# STM32F446RC_single_layer.net
KiCad netlist of a schematic drawn in EAGLE
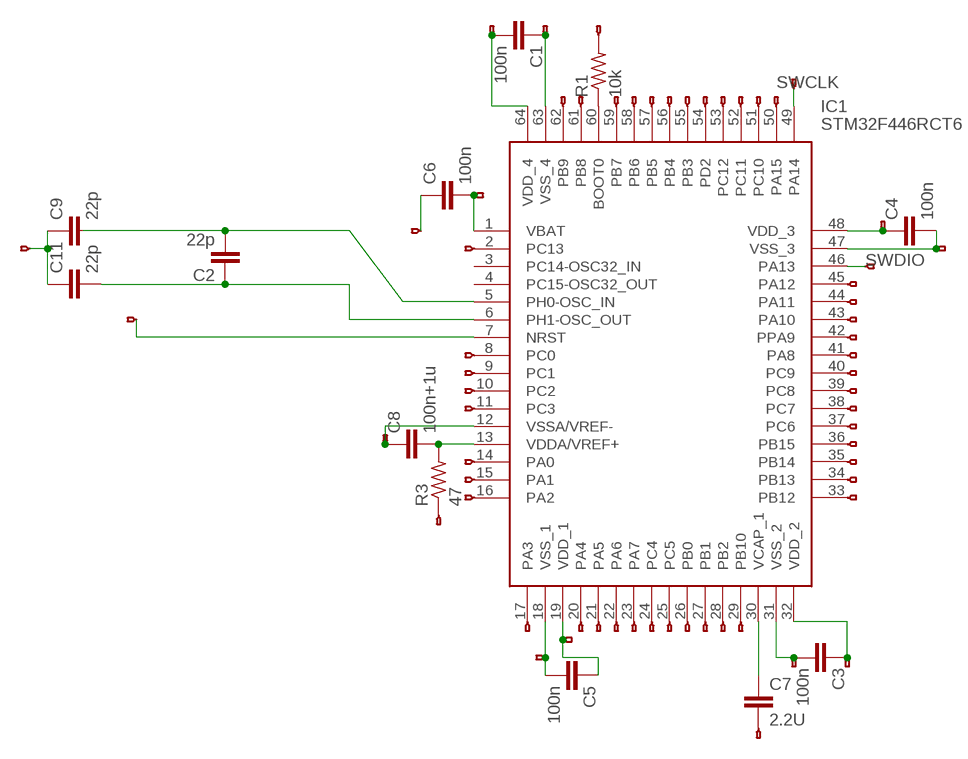
[diagram p0: schematic, sheet 1]

(export (version "E")
  (design (tool "Eeschema 10.0.6"))
  (components
    (comp (ref "C1")
      (value "100n")
      (footprint "eagle-import:C2.5-3")
      (libsource (lib "eagle-import") (part "C2,5-3"))
    )
    (comp (ref "C2")
      (value "22p")
      (footprint "eagle-import:C2.5-3")
      (libsource (lib "eagle-import") (part "C2,5-3"))
    )
    (comp (ref "C3")
      (value "100n")
      (footprint "eagle-import:C2.5-3")
      (libsource (lib "eagle-import") (part "C2,5-3"))
    )
    (comp (ref "C4")
      (value "100n")
      (footprint "eagle-import:C2.5-3")
      (libsource (lib "eagle-import") (part "C2,5-3"))
    )
    (comp (ref "C5")
      (value "100n")
      (footprint "eagle-import:C2.5-3")
      (libsource (lib "eagle-import") (part "C2,5-3"))
    )
    (comp (ref "C6")
      (value "100n")
      (footprint "eagle-import:C2.5-3")
      (libsource (lib "eagle-import") (part "C2,5-3"))
    )
    (comp (ref "C7")
      (value "2.2U")
      (footprint "eagle-import:C2.5-3")
      (libsource (lib "eagle-import") (part "C2,5-3"))
    )
    (comp (ref "C8")
      (value "100n+1u")
      (footprint "eagle-import:C2.5-3")
      (libsource (lib "eagle-import") (part "C2,5-3"))
    )
    (comp (ref "C9")
      (value "22p")
      (footprint "eagle-import:C2.5-3")
      (libsource (lib "eagle-import") (part "C2,5-3"))
    )
    (comp (ref "C11")
      (value "22p")
      (footprint "eagle-import:C2.5-3")
      (libsource (lib "eagle-import") (part "C2,5-3"))
    )
    (comp (ref "IC1")
      (value "STM32F446RCT6")
      (footprint "eagle-import:QFP50P1200X1200X160-64N")
      (fields (field (name "MOUSER_PART_NUMBER") "511-STM32F446RCT6"))
      (libsource (lib "eagle-import") (part "STM32F446RCT6"))
    )
    (comp (ref "JP1")
      (value "HEADERHOLE-HEADERHOLE")
      (footprint "eagle-import:1X1-HEADER-HOLE")
      (libsource (lib "eagle-import") (part "HEADERHOLE-HEADERHOLE"))
    )
    (comp (ref "JP2")
      (value "HEADERHOLE-HEADERHOLE")
      (footprint "eagle-import:1X1-HEADER-HOLE")
      (libsource (lib "eagle-import") (part "HEADERHOLE-HEADERHOLE"))
    )
    (comp (ref "JP3")
      (value "HEADERHOLE-HEADERHOLE")
      (footprint "eagle-import:1X1-HEADER-HOLE")
      (libsource (lib "eagle-import") (part "HEADERHOLE-HEADERHOLE"))
    )
    (comp (ref "JP4")
      (value "HEADERHOLE-HEADERHOLE")
      (footprint "eagle-import:1X1-HEADER-HOLE")
      (libsource (lib "eagle-import") (part "HEADERHOLE-HEADERHOLE"))
    )
    (comp (ref "JP5")
      (value "HEADERHOLE-HEADERHOLE")
      (footprint "eagle-import:1X1-HEADER-HOLE")
      (libsource (lib "eagle-import") (part "HEADERHOLE-HEADERHOLE"))
    )
    (comp (ref "JP6")
      (value "HEADERHOLE-HEADERHOLE")
      (footprint "eagle-import:1X1-HEADER-HOLE")
      (libsource (lib "eagle-import") (part "HEADERHOLE-HEADERHOLE"))
    )
    (comp (ref "JP7")
      (value "HEADERHOLE-HEADERHOLE")
      (footprint "eagle-import:1X1-HEADER-HOLE")
      (libsource (lib "eagle-import") (part "HEADERHOLE-HEADERHOLE"))
    )
    (comp (ref "JP9")
      (value "HEADERHOLE-HEADERHOLE")
      (footprint "eagle-import:1X1-HEADER-HOLE")
      (libsource (lib "eagle-import") (part "HEADERHOLE-HEADERHOLE"))
    )
    (comp (ref "JP10")
      (value "HEADERHOLE-HEADERHOLE")
      (footprint "eagle-import:1X1-HEADER-HOLE")
      (libsource (lib "eagle-import") (part "HEADERHOLE-HEADERHOLE"))
    )
    (comp (ref "JP11")
      (value "HEADERHOLE-HEADERHOLE")
      (footprint "eagle-import:1X1-HEADER-HOLE")
      (libsource (lib "eagle-import") (part "HEADERHOLE-HEADERHOLE"))
    )
    (comp (ref "JP12")
      (value "HEADERHOLE-HEADERHOLE")
      (footprint "eagle-import:1X1-HEADER-HOLE")
      (libsource (lib "eagle-import") (part "HEADERHOLE-HEADERHOLE"))
    )
    (comp (ref "JP13")
      (value "HEADERHOLE-HEADERHOLE")
      (footprint "eagle-import:1X1-HEADER-HOLE")
      (libsource (lib "eagle-import") (part "HEADERHOLE-HEADERHOLE"))
    )
    (comp (ref "JP14")
      (value "HEADERHOLE-HEADERHOLE")
      (footprint "eagle-import:1X1-HEADER-HOLE")
      (libsource (lib "eagle-import") (part "HEADERHOLE-HEADERHOLE"))
    )
    (comp (ref "JP15")
      (value "HEADERHOLE-HEADERHOLE")
      (footprint "eagle-import:1X1-HEADER-HOLE")
      (libsource (lib "eagle-import") (part "HEADERHOLE-HEADERHOLE"))
    )
    (comp (ref "JP16")
      (value "HEADERHOLE-HEADERHOLE")
      (footprint "eagle-import:1X1-HEADER-HOLE")
      (libsource (lib "eagle-import") (part "HEADERHOLE-HEADERHOLE"))
    )
    (comp (ref "JP17")
      (value "HEADERHOLE-HEADERHOLE")
      (footprint "eagle-import:1X1-HEADER-HOLE")
      (libsource (lib "eagle-import") (part "HEADERHOLE-HEADERHOLE"))
    )
    (comp (ref "JP18")
      (value "HEADERHOLE-HEADERHOLE")
      (footprint "eagle-import:1X1-HEADER-HOLE")
      (libsource (lib "eagle-import") (part "HEADERHOLE-HEADERHOLE"))
    )
    (comp (ref "JP19")
      (value "HEADERHOLE-HEADERHOLE")
      (footprint "eagle-import:1X1-HEADER-HOLE")
      (libsource (lib "eagle-import") (part "HEADERHOLE-HEADERHOLE"))
    )
    (comp (ref "JP20")
      (value "HEADERHOLE-HEADERHOLE")
      (footprint "eagle-import:1X1-HEADER-HOLE")
      (libsource (lib "eagle-import") (part "HEADERHOLE-HEADERHOLE"))
    )
    (comp (ref "JP21")
      (value "HEADERHOLE-HEADERHOLE")
      (footprint "eagle-import:1X1-HEADER-HOLE")
      (libsource (lib "eagle-import") (part "HEADERHOLE-HEADERHOLE"))
    )
    (comp (ref "JP22")
      (value "HEADERHOLE-HEADERHOLE")
      (footprint "eagle-import:1X1-HEADER-HOLE")
      (libsource (lib "eagle-import") (part "HEADERHOLE-HEADERHOLE"))
    )
    (comp (ref "JP23")
      (value "HEADERHOLE-HEADERHOLE")
      (footprint "eagle-import:1X1-HEADER-HOLE")
      (libsource (lib "eagle-import") (part "HEADERHOLE-HEADERHOLE"))
    )
    (comp (ref "JP24")
      (value "HEADERHOLE-HEADERHOLE")
      (footprint "eagle-import:1X1-HEADER-HOLE")
      (libsource (lib "eagle-import") (part "HEADERHOLE-HEADERHOLE"))
    )
    (comp (ref "JP25")
      (value "HEADERHOLE-HEADERHOLE")
      (footprint "eagle-import:1X1-HEADER-HOLE")
      (libsource (lib "eagle-import") (part "HEADERHOLE-HEADERHOLE"))
    )
    (comp (ref "JP26")
      (value "HEADERHOLE-HEADERHOLE")
      (footprint "eagle-import:1X1-HEADER-HOLE")
      (libsource (lib "eagle-import") (part "HEADERHOLE-HEADERHOLE"))
    )
    (comp (ref "JP27")
      (value "HEADERHOLE-HEADERHOLE")
      (footprint "eagle-import:1X1-HEADER-HOLE")
      (libsource (lib "eagle-import") (part "HEADERHOLE-HEADERHOLE"))
    )
    (comp (ref "JP28")
      (value "HEADERHOLE-HEADERHOLE")
      (footprint "eagle-import:1X1-HEADER-HOLE")
      (libsource (lib "eagle-import") (part "HEADERHOLE-HEADERHOLE"))
    )
    (comp (ref "JP29")
      (value "HEADERHOLE-HEADERHOLE")
      (footprint "eagle-import:1X1-HEADER-HOLE")
      (libsource (lib "eagle-import") (part "HEADERHOLE-HEADERHOLE"))
    )
    (comp (ref "JP30")
      (value "HEADERHOLE-HEADERHOLE")
      (footprint "eagle-import:1X1-HEADER-HOLE")
      (libsource (lib "eagle-import") (part "HEADERHOLE-HEADERHOLE"))
    )
    (comp (ref "JP31")
      (value "HEADERHOLE-HEADERHOLE")
      (footprint "eagle-import:1X1-HEADER-HOLE")
      (libsource (lib "eagle-import") (part "HEADERHOLE-HEADERHOLE"))
    )
    (comp (ref "JP32")
      (value "HEADERHOLE-HEADERHOLE")
      (footprint "eagle-import:1X1-HEADER-HOLE")
      (libsource (lib "eagle-import") (part "HEADERHOLE-HEADERHOLE"))
    )
    (comp (ref "JP33")
      (value "HEADERHOLE-HEADERHOLE")
      (footprint "eagle-import:1X1-HEADER-HOLE")
      (libsource (lib "eagle-import") (part "HEADERHOLE-HEADERHOLE"))
    )
    (comp (ref "JP34")
      (value "HEADERHOLE-HEADERHOLE")
      (footprint "eagle-import:1X1-HEADER-HOLE")
      (libsource (lib "eagle-import") (part "HEADERHOLE-HEADERHOLE"))
    )
    (comp (ref "JP35")
      (value "HEADERHOLE-HEADERHOLE")
      (footprint "eagle-import:1X1-HEADER-HOLE")
      (libsource (lib "eagle-import") (part "HEADERHOLE-HEADERHOLE"))
    )
    (comp (ref "JP36")
      (value "HEADERHOLE-HEADERHOLE")
      (footprint "eagle-import:1X1-HEADER-HOLE")
      (libsource (lib "eagle-import") (part "HEADERHOLE-HEADERHOLE"))
    )
    (comp (ref "JP37")
      (value "HEADERHOLE-HEADERHOLE")
      (footprint "eagle-import:1X1-HEADER-HOLE")
      (libsource (lib "eagle-import") (part "HEADERHOLE-HEADERHOLE"))
    )
    (comp (ref "JP38")
      (value "HEADERHOLE-HEADERHOLE")
      (footprint "eagle-import:1X1-HEADER-HOLE")
      (libsource (lib "eagle-import") (part "HEADERHOLE-HEADERHOLE"))
    )
    (comp (ref "JP39")
      (value "HEADERHOLE-HEADERHOLE")
      (footprint "eagle-import:1X1-HEADER-HOLE")
      (libsource (lib "eagle-import") (part "HEADERHOLE-HEADERHOLE"))
    )
    (comp (ref "JP40")
      (value "HEADERHOLE-HEADERHOLE")
      (footprint "eagle-import:1X1-HEADER-HOLE")
      (libsource (lib "eagle-import") (part "HEADERHOLE-HEADERHOLE"))
    )
    (comp (ref "JP41")
      (value "HEADERHOLE-HEADERHOLE")
      (footprint "eagle-import:1X1-HEADER-HOLE")
      (libsource (lib "eagle-import") (part "HEADERHOLE-HEADERHOLE"))
    )
    (comp (ref "JP42")
      (value "HEADERHOLE-HEADERHOLE")
      (footprint "eagle-import:1X1-HEADER-HOLE")
      (libsource (lib "eagle-import") (part "HEADERHOLE-HEADERHOLE"))
    )
    (comp (ref "JP43")
      (value "HEADERHOLE-HEADERHOLE")
      (footprint "eagle-import:1X1-HEADER-HOLE")
      (libsource (lib "eagle-import") (part "HEADERHOLE-HEADERHOLE"))
    )
    (comp (ref "JP44")
      (value "HEADERHOLE-HEADERHOLE")
      (footprint "eagle-import:1X1-HEADER-HOLE")
      (libsource (lib "eagle-import") (part "HEADERHOLE-HEADERHOLE"))
    )
    (comp (ref "JP45")
      (value "HEADERHOLE-HEADERHOLE")
      (footprint "eagle-import:1X1-HEADER-HOLE")
      (libsource (lib "eagle-import") (part "HEADERHOLE-HEADERHOLE"))
    )
    (comp (ref "JP46")
      (value "HEADERHOLE-HEADERHOLE")
      (footprint "eagle-import:1X1-HEADER-HOLE")
      (libsource (lib "eagle-import") (part "HEADERHOLE-HEADERHOLE"))
    )
    (comp (ref "JP47")
      (value "HEADERHOLE-HEADERHOLE")
      (footprint "eagle-import:1X1-HEADER-HOLE")
      (libsource (lib "eagle-import") (part "HEADERHOLE-HEADERHOLE"))
    )
    (comp (ref "JP48")
      (value "HEADERHOLE-HEADERHOLE")
      (footprint "eagle-import:1X1-HEADER-HOLE")
      (libsource (lib "eagle-import") (part "HEADERHOLE-HEADERHOLE"))
    )
    (comp (ref "JP49")
      (value "HEADERHOLE-HEADERHOLE")
      (footprint "eagle-import:1X1-HEADER-HOLE")
      (libsource (lib "eagle-import") (part "HEADERHOLE-HEADERHOLE"))
    )
    (comp (ref "JP50")
      (value "HEADERHOLE-HEADERHOLE")
      (footprint "eagle-import:1X1-HEADER-HOLE")
      (libsource (lib "eagle-import") (part "HEADERHOLE-HEADERHOLE"))
    )
    (comp (ref "JP51")
      (value "HEADERHOLE-HEADERHOLE")
      (footprint "eagle-import:1X1-HEADER-HOLE")
      (libsource (lib "eagle-import") (part "HEADERHOLE-HEADERHOLE"))
    )
    (comp (ref "JP52")
      (value "HEADERHOLE-HEADERHOLE")
      (footprint "eagle-import:1X1-HEADER-HOLE")
      (libsource (lib "eagle-import") (part "HEADERHOLE-HEADERHOLE"))
    )
    (comp (ref "JP53")
      (value "HEADERHOLE-HEADERHOLE")
      (footprint "eagle-import:1X1-HEADER-HOLE")
      (libsource (lib "eagle-import") (part "HEADERHOLE-HEADERHOLE"))
    )
    (comp (ref "JP54")
      (value "HEADERHOLE-HEADERHOLE")
      (footprint "eagle-import:1X1-HEADER-HOLE")
      (libsource (lib "eagle-import") (part "HEADERHOLE-HEADERHOLE"))
    )
    (comp (ref "JP55")
      (value "HEADERHOLE-HEADERHOLE")
      (footprint "eagle-import:1X1-HEADER-HOLE")
      (libsource (lib "eagle-import") (part "HEADERHOLE-HEADERHOLE"))
    )
    (comp (ref "JP56")
      (value "HEADERHOLE-HEADERHOLE")
      (footprint "eagle-import:1X1-HEADER-HOLE")
      (libsource (lib "eagle-import") (part "HEADERHOLE-HEADERHOLE"))
    )
    (comp (ref "JP57")
      (value "HEADERHOLE-HEADERHOLE")
      (footprint "eagle-import:1X1-HEADER-HOLE")
      (libsource (lib "eagle-import") (part "HEADERHOLE-HEADERHOLE"))
    )
    (comp (ref "JP58")
      (value "HEADERHOLE-HEADERHOLE")
      (footprint "eagle-import:1X1-HEADER-HOLE")
      (libsource (lib "eagle-import") (part "HEADERHOLE-HEADERHOLE"))
    )
    (comp (ref "JP59")
      (value "HEADERHOLE-HEADERHOLE")
      (footprint "eagle-import:1X1-HEADER-HOLE")
      (libsource (lib "eagle-import") (part "HEADERHOLE-HEADERHOLE"))
    )
    (comp (ref "JP61")
      (value "HEADERHOLE-HEADERHOLE")
      (footprint "eagle-import:1X1-HEADER-HOLE")
      (libsource (lib "eagle-import") (part "HEADERHOLE-HEADERHOLE"))
    )
    (comp (ref "JP62")
      (value "HEADERHOLE-HEADERHOLE")
      (footprint "eagle-import:1X1-HEADER-HOLE")
      (libsource (lib "eagle-import") (part "HEADERHOLE-HEADERHOLE"))
    )
    (comp (ref "JP63")
      (value "HEADERHOLE-HEADERHOLE")
      (footprint "eagle-import:1X1-HEADER-HOLE")
      (libsource (lib "eagle-import") (part "HEADERHOLE-HEADERHOLE"))
    )
    (comp (ref "JP65")
      (value "HEADERHOLE-HEADERHOLE")
      (footprint "eagle-import:1X1-HEADER-HOLE")
      (libsource (lib "eagle-import") (part "HEADERHOLE-HEADERHOLE"))
    )
    (comp (ref "R1")
      (value "10k")
      (footprint "eagle-import:0204V")
      (libsource (lib "eagle-import") (part "R-US_0204/2V"))
    )
    (comp (ref "R3")
      (value "47")
      (footprint "eagle-import:0204V")
      (libsource (lib "eagle-import") (part "R-US_0204/2V"))
    )
  )
  (nets
    (net (code "1") (name "/SWCLK") (class "Default")
      (node (ref "IC1") (pin "49") (pinfunction "PA14_49") (pintype "bidirectional"))
      (node (ref "JP55") (pin "1") (pinfunction "P$1_1") (pintype "bidirectional"))
    )
    (net (code "2") (name "/SWDIO") (class "Default")
      (node (ref "IC1") (pin "46") (pinfunction "PA13_46") (pintype "bidirectional"))
      (node (ref "JP54") (pin "1") (pinfunction "P$1_1") (pintype "bidirectional"))
    )
    (net (code "3") (name "Net-(IC1-BOOT0)") (class "Default")
      (node (ref "IC1") (pin "60") (pinfunction "BOOT0_60") (pintype "bidirectional"))
      (node (ref "R1") (pin "1") (pinfunction "1_1") (pintype "passive"))
    )
    (net (code "4") (name "Net-(IC1-NRST)") (class "Default")
      (node (ref "IC1") (pin "7") (pinfunction "NRST_7") (pintype "bidirectional"))
      (node (ref "JP63") (pin "1") (pinfunction "P$1_1") (pintype "bidirectional"))
    )
    (net (code "5") (name "Net-(IC1-PA0)") (class "Default")
      (node (ref "IC1") (pin "14") (pinfunction "PA0_14") (pintype "bidirectional"))
      (node (ref "JP34") (pin "1") (pinfunction "P$1_1") (pintype "bidirectional"))
    )
    (net (code "6") (name "Net-(IC1-PA1)") (class "Default")
      (node (ref "IC1") (pin "15") (pinfunction "PA1_15") (pintype "bidirectional"))
      (node (ref "JP35") (pin "1") (pinfunction "P$1_1") (pintype "bidirectional"))
    )
    (net (code "7") (name "Net-(IC1-PA2)") (class "Default")
      (node (ref "IC1") (pin "16") (pinfunction "PA2_16") (pintype "bidirectional"))
      (node (ref "JP36") (pin "1") (pinfunction "P$1_1") (pintype "bidirectional"))
    )
    (net (code "8") (name "Net-(IC1-PA3)") (class "Default")
      (node (ref "IC1") (pin "17") (pinfunction "PA3_17") (pintype "bidirectional"))
      (node (ref "JP24") (pin "1") (pinfunction "P$1_1") (pintype "bidirectional"))
    )
    (net (code "9") (name "Net-(IC1-PA4)") (class "Default")
      (node (ref "IC1") (pin "20") (pinfunction "PA4_20") (pintype "bidirectional"))
      (node (ref "JP21") (pin "1") (pinfunction "P$1_1") (pintype "bidirectional"))
    )
    (net (code "10") (name "Net-(IC1-PA5)") (class "Default")
      (node (ref "IC1") (pin "21") (pinfunction "PA5_21") (pintype "bidirectional"))
      (node (ref "JP19") (pin "1") (pinfunction "P$1_1") (pintype "bidirectional"))
    )
    (net (code "11") (name "Net-(IC1-PA6)") (class "Default")
      (node (ref "IC1") (pin "22") (pinfunction "PA6_22") (pintype "bidirectional"))
      (node (ref "JP9") (pin "1") (pinfunction "P$1_1") (pintype "bidirectional"))
    )
    (net (code "12") (name "Net-(IC1-PA7)") (class "Default")
      (node (ref "IC1") (pin "23") (pinfunction "PA7_23") (pintype "bidirectional"))
      (node (ref "JP11") (pin "1") (pinfunction "P$1_1") (pintype "bidirectional"))
    )
    (net (code "13") (name "Net-(IC1-PA8)") (class "Default")
      (node (ref "IC1") (pin "41") (pinfunction "PA8_41") (pintype "bidirectional"))
      (node (ref "JP28") (pin "1") (pinfunction "P$1_1") (pintype "bidirectional"))
    )
    (net (code "14") (name "Net-(IC1-PA10)") (class "Default")
      (node (ref "IC1") (pin "43") (pinfunction "PA10_43") (pintype "bidirectional"))
      (node (ref "JP33") (pin "1") (pinfunction "P$1_1") (pintype "bidirectional"))
    )
    (net (code "15") (name "Net-(IC1-PA11)") (class "Default")
      (node (ref "IC1") (pin "44") (pinfunction "PA11_44") (pintype "bidirectional"))
      (node (ref "JP32") (pin "1") (pinfunction "P$1_1") (pintype "bidirectional"))
    )
    (net (code "16") (name "Net-(IC1-PA12)") (class "Default")
      (node (ref "IC1") (pin "45") (pinfunction "PA12_45") (pintype "bidirectional"))
      (node (ref "JP25") (pin "1") (pinfunction "P$1_1") (pintype "bidirectional"))
    )
    (net (code "17") (name "Net-(IC1-PA15)") (class "Default")
      (node (ref "IC1") (pin "50") (pinfunction "PA15_50") (pintype "bidirectional"))
      (node (ref "JP45") (pin "1") (pinfunction "P$1_1") (pintype "bidirectional"))
    )
    (net (code "18") (name "Net-(IC1-PB0)") (class "Default")
      (node (ref "IC1") (pin "26") (pinfunction "PB0_26") (pintype "bidirectional"))
      (node (ref "JP22") (pin "1") (pinfunction "P$1_1") (pintype "bidirectional"))
    )
    (net (code "19") (name "Net-(IC1-PB1)") (class "Default")
      (node (ref "IC1") (pin "27") (pinfunction "PB1_27") (pintype "bidirectional"))
      (node (ref "JP17") (pin "1") (pinfunction "P$1_1") (pintype "bidirectional"))
    )
    (net (code "20") (name "Net-(IC1-PB2)") (class "Default")
      (node (ref "IC1") (pin "28") (pinfunction "PB2_28") (pintype "bidirectional"))
      (node (ref "JP16") (pin "1") (pinfunction "P$1_1") (pintype "bidirectional"))
    )
    (net (code "21") (name "Net-(IC1-PB3)") (class "Default")
      (node (ref "IC1") (pin "55") (pinfunction "PB3_55") (pintype "bidirectional"))
      (node (ref "JP44") (pin "1") (pinfunction "P$1_1") (pintype "bidirectional"))
    )
    (net (code "22") (name "Net-(IC1-PB4)") (class "Default")
      (node (ref "IC1") (pin "56") (pinfunction "PB4_56") (pintype "bidirectional"))
      (node (ref "JP40") (pin "1") (pinfunction "P$1_1") (pintype "bidirectional"))
    )
    (net (code "23") (name "Net-(IC1-PB5)") (class "Default")
      (node (ref "IC1") (pin "57") (pinfunction "PB5_57") (pintype "bidirectional"))
      (node (ref "JP41") (pin "1") (pinfunction "P$1_1") (pintype "bidirectional"))
    )
    (net (code "24") (name "Net-(IC1-PB6)") (class "Default")
      (node (ref "IC1") (pin "58") (pinfunction "PB6_58") (pintype "bidirectional"))
      (node (ref "JP42") (pin "1") (pinfunction "P$1_1") (pintype "bidirectional"))
    )
    (net (code "25") (name "Net-(IC1-PB7)") (class "Default")
      (node (ref "IC1") (pin "59") (pinfunction "PB7_59") (pintype "bidirectional"))
      (node (ref "JP43") (pin "1") (pinfunction "P$1_1") (pintype "bidirectional"))
    )
    (net (code "26") (name "Net-(IC1-PB8)") (class "Default")
      (node (ref "IC1") (pin "61") (pinfunction "PB8_61") (pintype "bidirectional"))
      (node (ref "JP46") (pin "1") (pinfunction "P$1_1") (pintype "bidirectional"))
    )
    (net (code "27") (name "Net-(IC1-PB9)") (class "Default")
      (node (ref "IC1") (pin "62") (pinfunction "PB9_62") (pintype "bidirectional"))
      (node (ref "JP47") (pin "1") (pinfunction "P$1_1") (pintype "bidirectional"))
    )
    (net (code "28") (name "Net-(IC1-PB10)") (class "Default")
      (node (ref "IC1") (pin "29") (pinfunction "PB10_29") (pintype "bidirectional"))
      (node (ref "JP14") (pin "1") (pinfunction "P$1_1") (pintype "bidirectional"))
    )
    (net (code "29") (name "Net-(IC1-PB12)") (class "Default")
      (node (ref "IC1") (pin "33") (pinfunction "PB12_33") (pintype "bidirectional"))
      (node (ref "JP18") (pin "1") (pinfunction "P$1_1") (pintype "bidirectional"))
    )
    (net (code "30") (name "Net-(IC1-PB13)") (class "Default")
      (node (ref "IC1") (pin "34") (pinfunction "PB13_34") (pintype "bidirectional"))
      (node (ref "JP13") (pin "1") (pinfunction "P$1_1") (pintype "bidirectional"))
    )
    (net (code "31") (name "Net-(IC1-PB14)") (class "Default")
      (node (ref "IC1") (pin "35") (pinfunction "PB14_35") (pintype "bidirectional"))
      (node (ref "JP6") (pin "1") (pinfunction "P$1_1") (pintype "bidirectional"))
    )
    (net (code "32") (name "Net-(IC1-PB15)") (class "Default")
      (node (ref "IC1") (pin "36") (pinfunction "PB15_36") (pintype "bidirectional"))
      (node (ref "JP10") (pin "1") (pinfunction "P$1_1") (pintype "bidirectional"))
    )
    (net (code "33") (name "Net-(IC1-PC0)") (class "Default")
      (node (ref "IC1") (pin "8") (pinfunction "PC0_8") (pintype "bidirectional"))
      (node (ref "JP29") (pin "1") (pinfunction "P$1_1") (pintype "bidirectional"))
    )
    (net (code "34") (name "Net-(IC1-PC1)") (class "Default")
      (node (ref "IC1") (pin "9") (pinfunction "PC1_9") (pintype "bidirectional"))
      (node (ref "JP27") (pin "1") (pinfunction "P$1_1") (pintype "bidirectional"))
    )
    (net (code "35") (name "Net-(IC1-PC2)") (class "Default")
      (node (ref "IC1") (pin "10") (pinfunction "PC2_10") (pintype "bidirectional"))
      (node (ref "JP3") (pin "1") (pinfunction "P$1_1") (pintype "bidirectional"))
    )
    (net (code "36") (name "Net-(IC1-PC3)") (class "Default")
      (node (ref "IC1") (pin "11") (pinfunction "PC3_11") (pintype "bidirectional"))
      (node (ref "JP4") (pin "1") (pinfunction "P$1_1") (pintype "bidirectional"))
    )
    (net (code "37") (name "Net-(IC1-PC4)") (class "Default")
      (node (ref "IC1") (pin "24") (pinfunction "PC4_24") (pintype "bidirectional"))
      (node (ref "JP12") (pin "1") (pinfunction "P$1_1") (pintype "bidirectional"))
    )
    (net (code "38") (name "Net-(IC1-PC5)") (class "Default")
      (node (ref "IC1") (pin "25") (pinfunction "PC5_25") (pintype "bidirectional"))
      (node (ref "JP23") (pin "1") (pinfunction "P$1_1") (pintype "bidirectional"))
    )
    (net (code "39") (name "Net-(IC1-PC6)") (class "Default")
      (node (ref "IC1") (pin "37") (pinfunction "PC6_37") (pintype "bidirectional"))
      (node (ref "JP1") (pin "1") (pinfunction "P$1_1") (pintype "bidirectional"))
    )
    (net (code "40") (name "Net-(IC1-PC7)") (class "Default")
      (node (ref "IC1") (pin "38") (pinfunction "PC7_38") (pintype "bidirectional"))
      (node (ref "JP15") (pin "1") (pinfunction "P$1_1") (pintype "bidirectional"))
    )
    (net (code "41") (name "Net-(IC1-PC8)") (class "Default")
      (node (ref "IC1") (pin "39") (pinfunction "PC8_39") (pintype "bidirectional"))
      (node (ref "JP2") (pin "1") (pinfunction "P$1_1") (pintype "bidirectional"))
    )
    (net (code "42") (name "Net-(IC1-PC9)") (class "Default")
      (node (ref "IC1") (pin "40") (pinfunction "PC9_40") (pintype "bidirectional"))
      (node (ref "JP30") (pin "1") (pinfunction "P$1_1") (pintype "bidirectional"))
    )
    (net (code "43") (name "Net-(IC1-PC10)") (class "Default")
      (node (ref "IC1") (pin "51") (pinfunction "PC10_51") (pintype "bidirectional"))
      (node (ref "JP37") (pin "1") (pinfunction "P$1_1") (pintype "bidirectional"))
    )
    (net (code "44") (name "Net-(IC1-PC11)") (class "Default")
      (node (ref "IC1") (pin "52") (pinfunction "PC11_52") (pintype "bidirectional"))
      (node (ref "JP5") (pin "1") (pinfunction "P$1_1") (pintype "bidirectional"))
    )
    (net (code "45") (name "Net-(IC1-PC12)") (class "Default")
      (node (ref "IC1") (pin "53") (pinfunction "PC12_53") (pintype "bidirectional"))
      (node (ref "JP39") (pin "1") (pinfunction "P$1_1") (pintype "bidirectional"))
    )
    (net (code "46") (name "Net-(IC1-PC13)") (class "Default")
      (node (ref "IC1") (pin "2") (pinfunction "PC13_2") (pintype "bidirectional"))
      (node (ref "JP26") (pin "1") (pinfunction "P$1_1") (pintype "bidirectional"))
    )
    (net (code "47") (name "Net-(IC1-PD2)") (class "Default")
      (node (ref "IC1") (pin "54") (pinfunction "PD2_54") (pintype "bidirectional"))
      (node (ref "JP38") (pin "1") (pinfunction "P$1_1") (pintype "bidirectional"))
    )
    (net (code "48") (name "Net-(IC1-PH0-OSC_IN)") (class "Default")
      (node (ref "C2") (pin "2") (pinfunction "2_2") (pintype "passive"))
      (node (ref "IC1") (pin "5") (pinfunction "PH0-OSC_IN_5") (pintype "bidirectional"))
    )
    (net (code "49") (name "Net-(IC1-PH1-OSC_OUT)") (class "Default")
      (node (ref "C11") (pin "2") (pinfunction "2_2") (pintype "passive"))
      (node (ref "C2") (pin "1") (pinfunction "1_1") (pintype "passive"))
      (node (ref "IC1") (pin "6") (pinfunction "PH1-OSC_OUT_6") (pintype "bidirectional"))
    )
    (net (code "50") (name "Net-(IC1-PPA9)") (class "Default")
      (node (ref "IC1") (pin "42") (pinfunction "PPA9_42") (pintype "bidirectional"))
      (node (ref "JP31") (pin "1") (pinfunction "P$1_1") (pintype "bidirectional"))
    )
    (net (code "51") (name "Net-(IC1-VBAT)") (class "Default")
      (node (ref "C6") (pin "2") (pinfunction "2_2") (pintype "passive"))
      (node (ref "IC1") (pin "1") (pinfunction "VBAT_1") (pintype "bidirectional"))
      (node (ref "JP7") (pin "1") (pinfunction "P$1_1") (pintype "bidirectional"))
    )
    (net (code "52") (name "Net-(IC1-VCAP_1)") (class "Default")
      (node (ref "C7") (pin "1") (pinfunction "1_1") (pintype "passive"))
      (node (ref "IC1") (pin "30") (pinfunction "VCAP_1_30") (pintype "bidirectional"))
    )
    (net (code "53") (name "Net-(IC1-VDDA{slash}VREF+)") (class "Default")
      (node (ref "C8") (pin "2") (pinfunction "2_2") (pintype "passive"))
      (node (ref "IC1") (pin "13") (pinfunction "VDDA/VREF+_13") (pintype "bidirectional"))
      (node (ref "R3") (pin "2") (pinfunction "2_2") (pintype "passive"))
    )
    (net (code "54") (name "Net-(IC1-VDD_1)") (class "Default")
      (node (ref "C5") (pin "1") (pinfunction "1_1") (pintype "passive"))
      (node (ref "IC1") (pin "19") (pinfunction "VDD_1_19") (pintype "bidirectional"))
      (node (ref "JP48") (pin "1") (pinfunction "P$1_1") (pintype "bidirectional"))
    )
    (net (code "55") (name "Net-(IC1-VDD_2)") (class "Default")
      (node (ref "C3") (pin "1") (pinfunction "1_1") (pintype "passive"))
      (node (ref "IC1") (pin "32") (pinfunction "VDD_2_32") (pintype "bidirectional"))
      (node (ref "JP51") (pin "1") (pinfunction "P$1_1") (pintype "bidirectional"))
    )
    (net (code "56") (name "Net-(IC1-VDD_3)") (class "Default")
      (node (ref "C4") (pin "1") (pinfunction "1_1") (pintype "passive"))
      (node (ref "IC1") (pin "48") (pinfunction "VDD_3_48") (pintype "bidirectional"))
      (node (ref "JP53") (pin "1") (pinfunction "P$1_1") (pintype "bidirectional"))
    )
    (net (code "57") (name "Net-(IC1-VDD_4)") (class "Default")
      (node (ref "C1") (pin "2") (pinfunction "2_2") (pintype "passive"))
      (node (ref "IC1") (pin "64") (pinfunction "VDD_4_64") (pintype "bidirectional"))
      (node (ref "JP58") (pin "1") (pinfunction "P$1_1") (pintype "bidirectional"))
    )
    (net (code "58") (name "Net-(IC1-VSSA{slash}VREF-)") (class "Default")
      (node (ref "C8") (pin "1") (pinfunction "1_1") (pintype "passive"))
      (node (ref "IC1") (pin "12") (pinfunction "VSSA/VREF-_12") (pintype "bidirectional"))
      (node (ref "JP62") (pin "1") (pinfunction "P$1_1") (pintype "bidirectional"))
    )
    (net (code "59") (name "Net-(IC1-VSS_1)") (class "Default")
      (node (ref "C5") (pin "2") (pinfunction "2_2") (pintype "passive"))
      (node (ref "IC1") (pin "18") (pinfunction "VSS_1_18") (pintype "bidirectional"))
      (node (ref "JP20") (pin "1") (pinfunction "P$1_1") (pintype "bidirectional"))
    )
    (net (code "60") (name "Net-(IC1-VSS_2)") (class "Default")
      (node (ref "C3") (pin "2") (pinfunction "2_2") (pintype "passive"))
      (node (ref "IC1") (pin "31") (pinfunction "VSS_2_31") (pintype "bidirectional"))
      (node (ref "JP50") (pin "1") (pinfunction "P$1_1") (pintype "bidirectional"))
    )
    (net (code "61") (name "Net-(IC1-VSS_3)") (class "Default")
      (node (ref "C4") (pin "2") (pinfunction "2_2") (pintype "passive"))
      (node (ref "IC1") (pin "47") (pinfunction "VSS_3_47") (pintype "bidirectional"))
      (node (ref "JP52") (pin "1") (pinfunction "P$1_1") (pintype "bidirectional"))
    )
    (net (code "62") (name "Net-(IC1-VSS_4)") (class "Default")
      (node (ref "C1") (pin "1") (pinfunction "1_1") (pintype "passive"))
      (node (ref "IC1") (pin "63") (pinfunction "VSS_4_63") (pintype "bidirectional"))
      (node (ref "JP57") (pin "1") (pinfunction "P$1_1") (pintype "bidirectional"))
    )
    (net (code "63") (name "Net-(JP49-P$1)") (class "Default")
      (node (ref "C7") (pin "2") (pinfunction "2_2") (pintype "passive"))
      (node (ref "JP49") (pin "1") (pinfunction "P$1_1") (pintype "bidirectional"))
    )
    (net (code "64") (name "Net-(JP56-P$1)") (class "Default")
      (node (ref "JP56") (pin "1") (pinfunction "P$1_1") (pintype "bidirectional"))
      (node (ref "R1") (pin "2") (pinfunction "2_2") (pintype "passive"))
    )
    (net (code "65") (name "Net-(JP59-P$1)") (class "Default")
      (node (ref "C6") (pin "1") (pinfunction "1_1") (pintype "passive"))
      (node (ref "JP59") (pin "1") (pinfunction "P$1_1") (pintype "bidirectional"))
    )
    (net (code "66") (name "Net-(JP61-P$1)") (class "Default")
      (node (ref "JP61") (pin "1") (pinfunction "P$1_1") (pintype "bidirectional"))
      (node (ref "R3") (pin "1") (pinfunction "1_1") (pintype "passive"))
    )
    (net (code "67") (name "Net-(JP65-P$1)") (class "Default")
      (node (ref "C11") (pin "1") (pinfunction "1_1") (pintype "passive"))
      (node (ref "C9") (pin "1") (pinfunction "1_1") (pintype "passive"))
      (node (ref "JP65") (pin "1") (pinfunction "P$1_1") (pintype "bidirectional"))
    )
    (net (code "68") (name "unconnected-(C9-Pad2)") (class "Default")
      (node (ref "C9") (pin "2") (pinfunction "2_2") (pintype "passive"))
    )
    (net (code "69") (name "unconnected-(IC1-PC14-OSC32_IN-Pad3)") (class "Default")
      (node (ref "IC1") (pin "3") (pinfunction "PC14-OSC32_IN_3") (pintype "bidirectional"))
    )
    (net (code "70") (name "unconnected-(IC1-PC15-OSC32_OUT-Pad4)") (class "Default")
      (node (ref "IC1") (pin "4") (pinfunction "PC15-OSC32_OUT_4") (pintype "bidirectional"))
    )
  )
)
